# mainboard_1_3.net
KiCad netlist of a schematic drawn in EAGLE
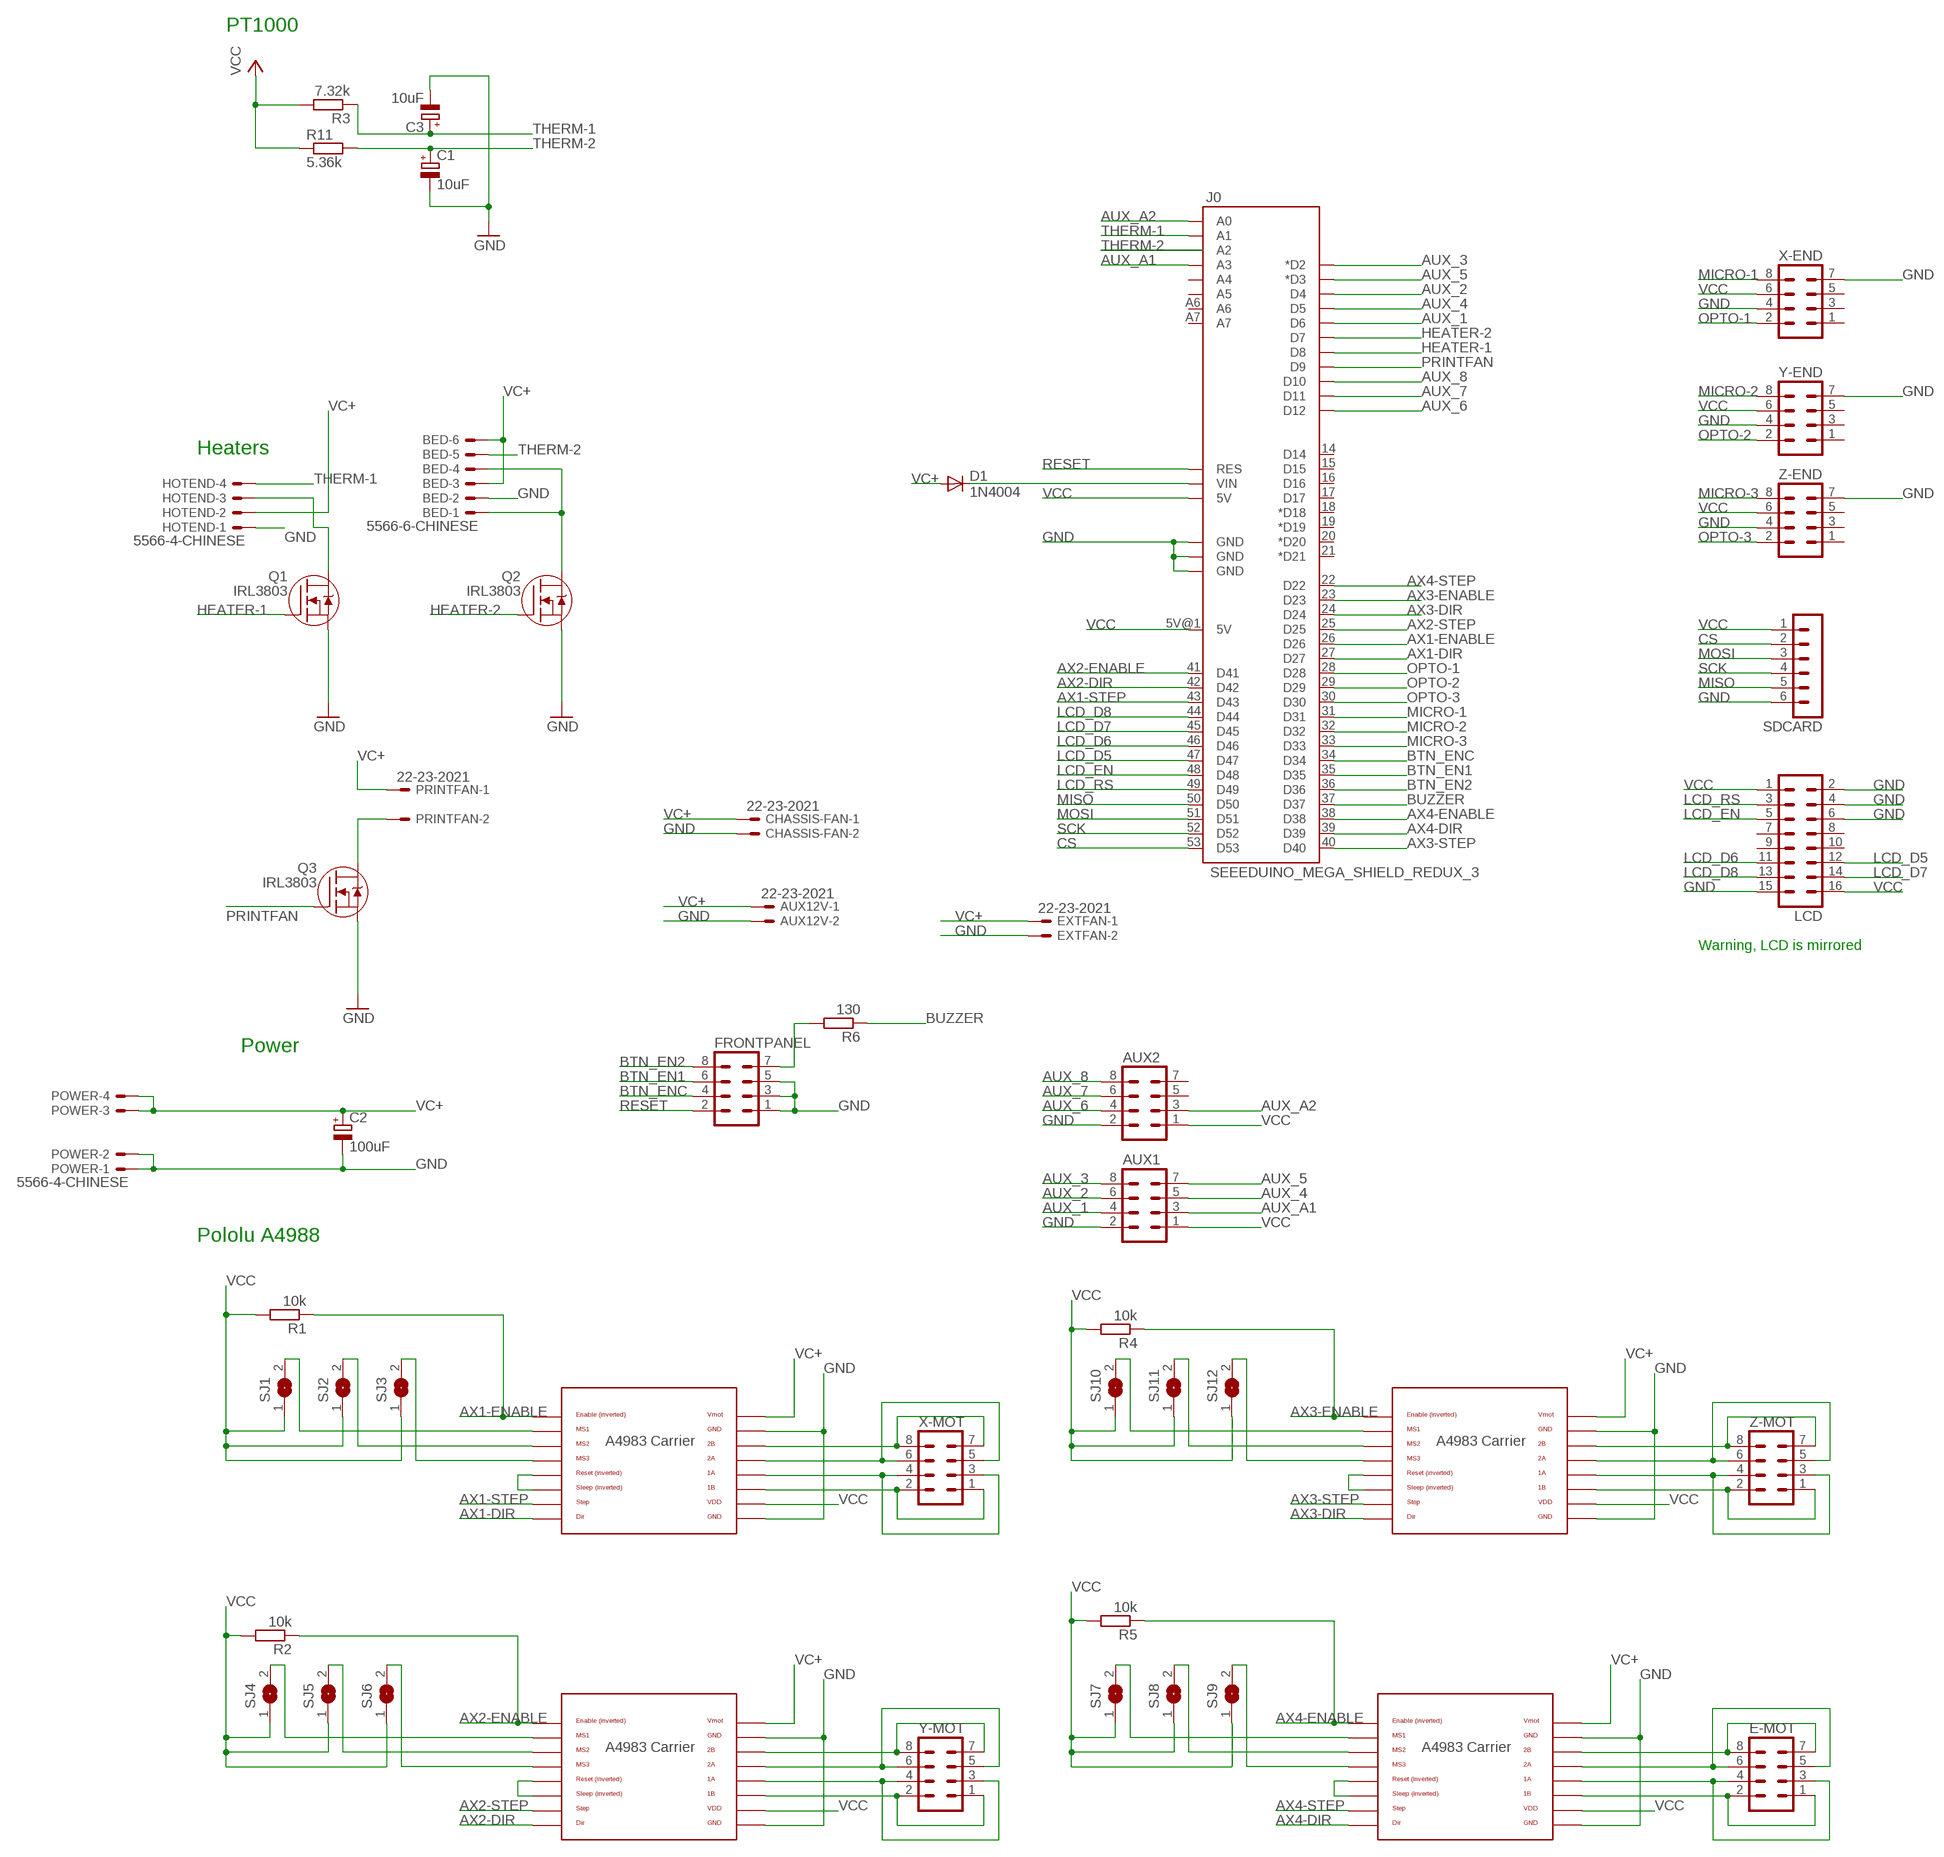
[diagram p0: schematic, sheet 1]

(export (version "E")
  (design (tool "Eeschema 10.0.6"))
  (components
    (comp (ref "AUX1")
      (value "MA04-2-HOLES")
      (footprint "eagle-import:MA04-2")
      (fields (field (name "OC_FARNELL") "unknown") (field (name "OC_NEWARK") "unknown"))
      (libsource (lib "eagle-import") (part "MA04-2-HOLES"))
    )
    (comp (ref "AUX2")
      (value "MA04-2")
      (footprint "eagle-import:MA04-2@1")
      (fields (field (name "OC_FARNELL") "unknown") (field (name "OC_NEWARK") "unknown"))
      (libsource (lib "eagle-import") (part "MA04-2"))
    )
    (comp (ref "AUX12V")
      (value "22-23-2021")
      (footprint "eagle-import:22-23-2021")
      (fields
        (field (name "MF") "MOLEX")
        (field (name "MF_1") "MOLEX")
        (field (name "MPN") "22-23-2021")
        (field (name "OC_FARNELL") "1462926")
        (field (name "OC_NEWARK") "25C3832")
      )
      (libsource (lib "eagle-import") (part "22-23-2021"))
    )
    (comp (ref "BED")
      (value "5566-6-CHINESE")
      (footprint "eagle-import:5566-6-CHINESE")
      (fields (field (name "MPN") "95566-61002"))
      (libsource (lib "eagle-import") (part "5566-6-CHINESE"))
    )
    (comp (ref "C1")
      (value "10uF")
      (footprint "eagle-import:E2,5-6")
      (libsource (lib "eagle-import") (part "CPOL-EUE2.5-6"))
    )
    (comp (ref "C2")
      (value "100uF")
      (footprint "eagle-import:E2,5-6")
      (libsource (lib "eagle-import") (part "CPOL-EUE2.5-6"))
    )
    (comp (ref "C3")
      (value "10uF")
      (footprint "eagle-import:E2,5-6")
      (libsource (lib "eagle-import") (part "CPOL-EUE2.5-6"))
    )
    (comp (ref "CHASSIS-FAN")
      (value "22-23-2021")
      (footprint "eagle-import:22-23-2021")
      (fields
        (field (name "MF") "MOLEX")
        (field (name "MF_1") "MOLEX")
        (field (name "MPN") "22-23-2021")
        (field (name "OC_FARNELL") "1462926")
        (field (name "OC_NEWARK") "25C3832")
      )
      (libsource (lib "eagle-import") (part "22-23-2021"))
    )
    (comp (ref "D1")
      (value "1N4004")
      (footprint "eagle-import:DO41-10")
      (libsource (lib "eagle-import") (part "1N4004"))
    )
    (comp (ref "E-AXIS")
      (value "POLOLU_A4983CARRIER")
      (footprint "eagle-import:A4983CARRIER")
      (libsource (lib "eagle-import") (part "POLOLU_A4983CARRIER"))
    )
    (comp (ref "E-MOT")
      (value "MA04-2")
      (footprint "eagle-import:MA04-2@1")
      (libsource (lib "eagle-import") (part "MA04-2"))
    )
    (comp (ref "EXTFAN")
      (value "22-23-2021")
      (footprint "eagle-import:22-23-2021")
      (fields
        (field (name "MF") "MOLEX")
        (field (name "MF_1") "MOLEX")
        (field (name "MPN") "22-23-2021")
        (field (name "OC_FARNELL") "1462926")
        (field (name "OC_NEWARK") "25C3832")
      )
      (libsource (lib "eagle-import") (part "22-23-2021"))
    )
    (comp (ref "FRONTPANEL")
      (value "MA04-2")
      (footprint "eagle-import:MA04-2@1")
      (libsource (lib "eagle-import") (part "MA04-2"))
    )
    (comp (ref "HOTEND")
      (value "5566-4-CHINESE")
      (footprint "eagle-import:5566-4-CHINESE")
      (libsource (lib "eagle-import") (part "5566-4-CHINESE"))
    )
    (comp (ref "J0")
      (value "SEEEDUINO_MEGA_SHIELD_REDUX_3")
      (footprint "eagle-import:SEEEDUINO_MEGA_SHIELD_REDUX_3")
      (libsource (lib "eagle-import") (part "SEEEDUINO_MEGA_SHIELD_REDUX_3"))
    )
    (comp (ref "LCD")
      (value "MA08-2")
      (footprint "eagle-import:MA08-2")
      (libsource (lib "eagle-import") (part "MA08-2"))
    )
    (comp (ref "POWER")
      (value "5566-4-CHINESE")
      (footprint "eagle-import:5566-4-CHINESE")
      (libsource (lib "eagle-import") (part "5566-4-CHINESE"))
    )
    (comp (ref "PRINTFAN")
      (value "22-23-2021")
      (footprint "eagle-import:22-23-2021")
      (fields (field (name "MF") "MOLEX"))
      (libsource (lib "eagle-import") (part "22-23-2021"))
    )
    (comp (ref "Q1")
      (value "IRL3803")
      (footprint "eagle-import:TO220AB")
      (libsource (lib "eagle-import") (part "IRL3803"))
    )
    (comp (ref "Q2")
      (value "IRL3803")
      (footprint "eagle-import:TO220AB")
      (libsource (lib "eagle-import") (part "IRL3803"))
    )
    (comp (ref "Q3")
      (value "IRL3803")
      (footprint "eagle-import:TO220AB")
      (libsource (lib "eagle-import") (part "IRL3803"))
    )
    (comp (ref "R1")
      (value "10k")
      (footprint "eagle-import:0204_7")
      (libsource (lib "eagle-import") (part "R-EU_0204/7"))
    )
    (comp (ref "R2")
      (value "10k")
      (footprint "eagle-import:0204_7")
      (libsource (lib "eagle-import") (part "R-EU_0204/7"))
    )
    (comp (ref "R3")
      (value "7.32k")
      (footprint "eagle-import:0204_7")
      (libsource (lib "eagle-import") (part "R-EU_0204/7"))
    )
    (comp (ref "R4")
      (value "10k")
      (footprint "eagle-import:0204_7")
      (libsource (lib "eagle-import") (part "R-EU_0204/7"))
    )
    (comp (ref "R5")
      (value "10k")
      (footprint "eagle-import:0204_7")
      (libsource (lib "eagle-import") (part "R-EU_0204/7"))
    )
    (comp (ref "R6")
      (value "130")
      (footprint "eagle-import:0204_7")
      (libsource (lib "eagle-import") (part "R-EU_0204/7"))
    )
    (comp (ref "R11")
      (value "5.36k")
      (footprint "eagle-import:0204_7")
      (libsource (lib "eagle-import") (part "R-EU_0204/7"))
    )
    (comp (ref "SDCARD")
      (value "MA06-1")
      (footprint "eagle-import:MA06-1")
      (libsource (lib "eagle-import") (part "MA06-1"))
    )
    (comp (ref "SJ1") (value "SJ") (footprint "eagle-import:SJ") (libsource (lib "eagle-import") (part "SJ")))
    (comp (ref "SJ2") (value "SJ") (footprint "eagle-import:SJ") (libsource (lib "eagle-import") (part "SJ")))
    (comp (ref "SJ3") (value "SJ") (footprint "eagle-import:SJ") (libsource (lib "eagle-import") (part "SJ")))
    (comp (ref "SJ4") (value "SJ") (footprint "eagle-import:SJ") (libsource (lib "eagle-import") (part "SJ")))
    (comp (ref "SJ5") (value "SJ") (footprint "eagle-import:SJ") (libsource (lib "eagle-import") (part "SJ")))
    (comp (ref "SJ6") (value "SJ") (footprint "eagle-import:SJ") (libsource (lib "eagle-import") (part "SJ")))
    (comp (ref "SJ7") (value "SJ") (footprint "eagle-import:SJ") (libsource (lib "eagle-import") (part "SJ")))
    (comp (ref "SJ8") (value "SJ") (footprint "eagle-import:SJ") (libsource (lib "eagle-import") (part "SJ")))
    (comp (ref "SJ9") (value "SJ") (footprint "eagle-import:SJ") (libsource (lib "eagle-import") (part "SJ")))
    (comp (ref "SJ10")
      (value "SJ")
      (footprint "eagle-import:SJ")
      (libsource (lib "eagle-import") (part "SJ"))
    )
    (comp (ref "SJ11")
      (value "SJ")
      (footprint "eagle-import:SJ")
      (libsource (lib "eagle-import") (part "SJ"))
    )
    (comp (ref "SJ12")
      (value "SJ")
      (footprint "eagle-import:SJ")
      (libsource (lib "eagle-import") (part "SJ"))
    )
    (comp (ref "X-AXIS")
      (value "POLOLU_A4983CARRIER")
      (footprint "eagle-import:A4983CARRIER")
      (libsource (lib "eagle-import") (part "POLOLU_A4983CARRIER"))
    )
    (comp (ref "X-END")
      (value "MA04-2")
      (footprint "eagle-import:MA04-2@1")
      (fields (field (name "OC_FARNELL") "unknown") (field (name "OC_NEWARK") "unknown"))
      (libsource (lib "eagle-import") (part "MA04-2"))
    )
    (comp (ref "X-MOT")
      (value "MA04-2")
      (footprint "eagle-import:MA04-2@1")
      (libsource (lib "eagle-import") (part "MA04-2"))
    )
    (comp (ref "Y-AXIS")
      (value "POLOLU_A4983CARRIER")
      (footprint "eagle-import:A4983CARRIER")
      (libsource (lib "eagle-import") (part "POLOLU_A4983CARRIER"))
    )
    (comp (ref "Y-END")
      (value "MA04-2")
      (footprint "eagle-import:MA04-2@1")
      (fields (field (name "OC_FARNELL") "unknown") (field (name "OC_NEWARK") "unknown"))
      (libsource (lib "eagle-import") (part "MA04-2"))
    )
    (comp (ref "Y-MOT")
      (value "MA04-2")
      (footprint "eagle-import:MA04-2@1")
      (libsource (lib "eagle-import") (part "MA04-2"))
    )
    (comp (ref "Z-AXIS")
      (value "POLOLU_A4983CARRIER")
      (footprint "eagle-import:A4983CARRIER")
      (libsource (lib "eagle-import") (part "POLOLU_A4983CARRIER"))
    )
    (comp (ref "Z-END")
      (value "MA04-2")
      (footprint "eagle-import:MA04-2@1")
      (fields (field (name "OC_FARNELL") "unknown") (field (name "OC_NEWARK") "unknown"))
      (libsource (lib "eagle-import") (part "MA04-2"))
    )
    (comp (ref "Z-MOT")
      (value "MA04-2")
      (footprint "eagle-import:MA04-2@1")
      (libsource (lib "eagle-import") (part "MA04-2"))
    )
  )
  (nets
    (net (code "1") (name "/AUX_1") (class "Default")
      (node (ref "AUX1") (pin "4") (pinfunction "4_4") (pintype "passive"))
      (node (ref "J0") (pin "6") (pinfunction "D6_6") (pintype "bidirectional"))
    )
    (net (code "2") (name "/AUX_2") (class "Default")
      (node (ref "AUX1") (pin "6") (pinfunction "6_6") (pintype "passive"))
      (node (ref "J0") (pin "4") (pinfunction "D4_4") (pintype "bidirectional"))
    )
    (net (code "3") (name "/AUX_3") (class "Default")
      (node (ref "AUX1") (pin "8") (pinfunction "8_8") (pintype "passive"))
      (node (ref "J0") (pin "2") (pinfunction "*D2_2") (pintype "bidirectional"))
    )
    (net (code "4") (name "/AUX_4") (class "Default")
      (node (ref "AUX1") (pin "5") (pinfunction "5_5") (pintype "passive"))
      (node (ref "J0") (pin "5") (pinfunction "D5_5") (pintype "bidirectional"))
    )
    (net (code "5") (name "/AUX_5") (class "Default")
      (node (ref "AUX1") (pin "7") (pinfunction "7_7") (pintype "passive"))
      (node (ref "J0") (pin "3") (pinfunction "*D3_3") (pintype "bidirectional"))
    )
    (net (code "6") (name "/AUX_6") (class "Default")
      (node (ref "AUX2") (pin "4") (pinfunction "4_4") (pintype "passive"))
      (node (ref "J0") (pin "12") (pinfunction "D12_12") (pintype "bidirectional"))
    )
    (net (code "7") (name "/AUX_7") (class "Default")
      (node (ref "AUX2") (pin "6") (pinfunction "6_6") (pintype "passive"))
      (node (ref "J0") (pin "11") (pinfunction "D11_11") (pintype "bidirectional"))
    )
    (net (code "8") (name "/AUX_8") (class "Default")
      (node (ref "AUX2") (pin "8") (pinfunction "8_8") (pintype "passive"))
      (node (ref "J0") (pin "10") (pinfunction "D10_10") (pintype "bidirectional"))
    )
    (net (code "9") (name "/AUX_A1") (class "Default")
      (node (ref "AUX1") (pin "3") (pinfunction "3_3") (pintype "passive"))
      (node (ref "J0") (pin "A3") (pinfunction "A3_A3") (pintype "bidirectional"))
    )
    (net (code "10") (name "/AUX_A2") (class "Default")
      (node (ref "AUX2") (pin "3") (pinfunction "3_3") (pintype "passive"))
      (node (ref "J0") (pin "A0") (pinfunction "A0_A0") (pintype "bidirectional"))
    )
    (net (code "11") (name "/AX1-DIR") (class "Default")
      (node (ref "J0") (pin "27") (pinfunction "D27_27") (pintype "bidirectional"))
      (node (ref "X-AXIS") (pin "DIR") (pinfunction "DIR_DIR") (pintype "input"))
    )
    (net (code "12") (name "/AX1-ENABLE") (class "Default")
      (node (ref "J0") (pin "26") (pinfunction "D26_26") (pintype "bidirectional"))
      (node (ref "R1") (pin "1") (pinfunction "1_1") (pintype "passive"))
      (node (ref "X-AXIS") (pin "EN") (pinfunction "EN_EN") (pintype "input"))
    )
    (net (code "13") (name "/AX1-STEP") (class "Default")
      (node (ref "J0") (pin "43") (pinfunction "D43_43") (pintype "bidirectional"))
      (node (ref "X-AXIS") (pin "STEP") (pinfunction "STEP_STEP") (pintype "input"))
    )
    (net (code "14") (name "/AX2-DIR") (class "Default")
      (node (ref "J0") (pin "42") (pinfunction "D42_42") (pintype "bidirectional"))
      (node (ref "Y-AXIS") (pin "DIR") (pinfunction "DIR_DIR") (pintype "input"))
    )
    (net (code "15") (name "/AX2-ENABLE") (class "Default")
      (node (ref "J0") (pin "41") (pinfunction "D41_41") (pintype "bidirectional"))
      (node (ref "R2") (pin "1") (pinfunction "1_1") (pintype "passive"))
      (node (ref "Y-AXIS") (pin "EN") (pinfunction "EN_EN") (pintype "input"))
    )
    (net (code "16") (name "/AX2-STEP") (class "Default")
      (node (ref "J0") (pin "25") (pinfunction "D25_25") (pintype "bidirectional"))
      (node (ref "Y-AXIS") (pin "STEP") (pinfunction "STEP_STEP") (pintype "input"))
    )
    (net (code "17") (name "/AX3-DIR") (class "Default")
      (node (ref "J0") (pin "24") (pinfunction "D24_24") (pintype "bidirectional"))
      (node (ref "Z-AXIS") (pin "DIR") (pinfunction "DIR_DIR") (pintype "input"))
    )
    (net (code "18") (name "/AX3-ENABLE") (class "Default")
      (node (ref "J0") (pin "23") (pinfunction "D23_23") (pintype "bidirectional"))
      (node (ref "R4") (pin "1") (pinfunction "1_1") (pintype "passive"))
      (node (ref "Z-AXIS") (pin "EN") (pinfunction "EN_EN") (pintype "input"))
    )
    (net (code "19") (name "/AX3-STEP") (class "Default")
      (node (ref "J0") (pin "40") (pinfunction "D40_40") (pintype "bidirectional"))
      (node (ref "Z-AXIS") (pin "STEP") (pinfunction "STEP_STEP") (pintype "input"))
    )
    (net (code "20") (name "/AX4-DIR") (class "Default")
      (node (ref "E-AXIS") (pin "DIR") (pinfunction "DIR_DIR") (pintype "input"))
      (node (ref "J0") (pin "39") (pinfunction "D39_39") (pintype "bidirectional"))
    )
    (net (code "21") (name "/AX4-ENABLE") (class "Default")
      (node (ref "E-AXIS") (pin "EN") (pinfunction "EN_EN") (pintype "input"))
      (node (ref "J0") (pin "38") (pinfunction "D38_38") (pintype "bidirectional"))
      (node (ref "R5") (pin "1") (pinfunction "1_1") (pintype "passive"))
    )
    (net (code "22") (name "/AX4-STEP") (class "Default")
      (node (ref "E-AXIS") (pin "STEP") (pinfunction "STEP_STEP") (pintype "input"))
      (node (ref "J0") (pin "22") (pinfunction "D22_22") (pintype "bidirectional"))
    )
    (net (code "23") (name "/BTN_EN1") (class "Default")
      (node (ref "FRONTPANEL") (pin "6") (pinfunction "6_6") (pintype "passive"))
      (node (ref "J0") (pin "35") (pinfunction "D35_35") (pintype "bidirectional"))
    )
    (net (code "24") (name "/BTN_EN2") (class "Default")
      (node (ref "FRONTPANEL") (pin "8") (pinfunction "8_8") (pintype "passive"))
      (node (ref "J0") (pin "36") (pinfunction "D36_36") (pintype "bidirectional"))
    )
    (net (code "25") (name "/BTN_ENC") (class "Default")
      (node (ref "FRONTPANEL") (pin "4") (pinfunction "4_4") (pintype "passive"))
      (node (ref "J0") (pin "34") (pinfunction "D34_34") (pintype "bidirectional"))
    )
    (net (code "26") (name "/BUZZER") (class "Default")
      (node (ref "J0") (pin "37") (pinfunction "D37_37") (pintype "bidirectional"))
      (node (ref "R6") (pin "1") (pinfunction "1_1") (pintype "passive"))
    )
    (net (code "27") (name "/CS") (class "Default")
      (node (ref "J0") (pin "53") (pinfunction "D53_53") (pintype "bidirectional"))
      (node (ref "SDCARD") (pin "2") (pinfunction "2_2") (pintype "passive"))
    )
    (net (code "28") (name "/HEATER-1") (class "Default")
      (node (ref "J0") (pin "8") (pinfunction "D8_8") (pintype "bidirectional"))
      (node (ref "Q1") (pin "G") (pinfunction "G_G") (pintype "bidirectional"))
    )
    (net (code "29") (name "/HEATER-2") (class "Default")
      (node (ref "J0") (pin "7") (pinfunction "D7_7") (pintype "bidirectional"))
      (node (ref "Q2") (pin "G") (pinfunction "G_G") (pintype "bidirectional"))
    )
    (net (code "30") (name "/LCD_D5") (class "Default")
      (node (ref "J0") (pin "47") (pinfunction "D47_47") (pintype "bidirectional"))
      (node (ref "LCD") (pin "12") (pinfunction "12_12") (pintype "passive"))
    )
    (net (code "31") (name "/LCD_D6") (class "Default")
      (node (ref "J0") (pin "46") (pinfunction "D46_46") (pintype "bidirectional"))
      (node (ref "LCD") (pin "11") (pinfunction "11_11") (pintype "passive"))
    )
    (net (code "32") (name "/LCD_D7") (class "Default")
      (node (ref "J0") (pin "45") (pinfunction "D45_45") (pintype "bidirectional"))
      (node (ref "LCD") (pin "14") (pinfunction "14_14") (pintype "passive"))
    )
    (net (code "33") (name "/LCD_D8") (class "Default")
      (node (ref "J0") (pin "44") (pinfunction "D44_44") (pintype "bidirectional"))
      (node (ref "LCD") (pin "13") (pinfunction "13_13") (pintype "passive"))
    )
    (net (code "34") (name "/LCD_EN") (class "Default")
      (node (ref "J0") (pin "48") (pinfunction "D48_48") (pintype "bidirectional"))
      (node (ref "LCD") (pin "5") (pinfunction "5_5") (pintype "passive"))
    )
    (net (code "35") (name "/LCD_RS") (class "Default")
      (node (ref "J0") (pin "49") (pinfunction "D49_49") (pintype "bidirectional"))
      (node (ref "LCD") (pin "3") (pinfunction "3_3") (pintype "passive"))
    )
    (net (code "36") (name "/MICRO-1") (class "Default")
      (node (ref "J0") (pin "31") (pinfunction "D31_31") (pintype "bidirectional"))
      (node (ref "X-END") (pin "8") (pinfunction "8_8") (pintype "passive"))
    )
    (net (code "37") (name "/MICRO-2") (class "Default")
      (node (ref "J0") (pin "32") (pinfunction "D32_32") (pintype "bidirectional"))
      (node (ref "Y-END") (pin "8") (pinfunction "8_8") (pintype "passive"))
    )
    (net (code "38") (name "/MICRO-3") (class "Default")
      (node (ref "J0") (pin "33") (pinfunction "D33_33") (pintype "bidirectional"))
      (node (ref "Z-END") (pin "8") (pinfunction "8_8") (pintype "passive"))
    )
    (net (code "39") (name "/MISO") (class "Default")
      (node (ref "J0") (pin "50") (pinfunction "D50_50") (pintype "bidirectional"))
      (node (ref "SDCARD") (pin "5") (pinfunction "5_5") (pintype "passive"))
    )
    (net (code "40") (name "/MOSI") (class "Default")
      (node (ref "J0") (pin "51") (pinfunction "D51_51") (pintype "bidirectional"))
      (node (ref "SDCARD") (pin "3") (pinfunction "3_3") (pintype "passive"))
    )
    (net (code "41") (name "/OPTO-1") (class "Default")
      (node (ref "J0") (pin "28") (pinfunction "D28_28") (pintype "bidirectional"))
      (node (ref "X-END") (pin "2") (pinfunction "2_2") (pintype "passive"))
    )
    (net (code "42") (name "/OPTO-2") (class "Default")
      (node (ref "J0") (pin "29") (pinfunction "D29_29") (pintype "bidirectional"))
      (node (ref "Y-END") (pin "2") (pinfunction "2_2") (pintype "passive"))
    )
    (net (code "43") (name "/OPTO-3") (class "Default")
      (node (ref "J0") (pin "30") (pinfunction "D30_30") (pintype "bidirectional"))
      (node (ref "Z-END") (pin "2") (pinfunction "2_2") (pintype "passive"))
    )
    (net (code "44") (name "/PRINTFAN") (class "Default")
      (node (ref "J0") (pin "9") (pinfunction "D9_9") (pintype "bidirectional"))
      (node (ref "Q3") (pin "G") (pinfunction "G_G") (pintype "bidirectional"))
    )
    (net (code "45") (name "/RESET") (class "Default")
      (node (ref "FRONTPANEL") (pin "2") (pinfunction "2_2") (pintype "passive"))
      (node (ref "J0") (pin "RST") (pinfunction "RES_RST") (pintype "bidirectional"))
    )
    (net (code "46") (name "/SCK") (class "Default")
      (node (ref "J0") (pin "52") (pinfunction "D52_52") (pintype "bidirectional"))
      (node (ref "SDCARD") (pin "4") (pinfunction "4_4") (pintype "passive"))
    )
    (net (code "47") (name "/THERM-1") (class "Default")
      (node (ref "C3") (pin "+") (pinfunction "+_+") (pintype "passive"))
      (node (ref "HOTEND") (pin "4") (pinfunction "S_4") (pintype "passive"))
      (node (ref "J0") (pin "A1") (pinfunction "A1_A1") (pintype "bidirectional"))
      (node (ref "R3") (pin "1") (pinfunction "1_1") (pintype "passive"))
    )
    (net (code "48") (name "/THERM-2") (class "Default")
      (node (ref "BED") (pin "5") (pinfunction "S_5") (pintype "passive"))
      (node (ref "C1") (pin "+") (pinfunction "+_+") (pintype "passive"))
      (node (ref "J0") (pin "A2") (pinfunction "A2_A2") (pintype "bidirectional"))
      (node (ref "R11") (pin "2") (pinfunction "2_2") (pintype "passive"))
    )
    (net (code "49") (name "/VC+") (class "Default")
      (node (ref "AUX12V") (pin "1") (pinfunction "S_1") (pintype "passive"))
      (node (ref "BED") (pin "3") (pinfunction "S_3") (pintype "passive"))
      (node (ref "BED") (pin "6") (pinfunction "S_6") (pintype "passive"))
      (node (ref "C2") (pin "+") (pinfunction "+_+") (pintype "passive"))
      (node (ref "CHASSIS-FAN") (pin "1") (pinfunction "S_1") (pintype "passive"))
      (node (ref "D1") (pin "A") (pinfunction "A_A") (pintype "passive"))
      (node (ref "E-AXIS") (pin "VMOT") (pinfunction "VMOT_VMOT") (pintype "power_in"))
      (node (ref "EXTFAN") (pin "1") (pinfunction "S_1") (pintype "passive"))
      (node (ref "HOTEND") (pin "2") (pinfunction "S_2") (pintype "passive"))
      (node (ref "POWER") (pin "3") (pinfunction "S_3") (pintype "passive"))
      (node (ref "POWER") (pin "4") (pinfunction "S_4") (pintype "passive"))
      (node (ref "PRINTFAN") (pin "1") (pinfunction "S_1") (pintype "passive"))
      (node (ref "X-AXIS") (pin "VMOT") (pinfunction "VMOT_VMOT") (pintype "power_in"))
      (node (ref "Y-AXIS") (pin "VMOT") (pinfunction "VMOT_VMOT") (pintype "power_in"))
      (node (ref "Z-AXIS") (pin "VMOT") (pinfunction "VMOT_VMOT") (pintype "power_in"))
    )
    (net (code "50") (name "GND") (class "Default")
      (node (ref "AUX1") (pin "2") (pinfunction "2_2") (pintype "passive"))
      (node (ref "AUX12V") (pin "2") (pinfunction "S_2") (pintype "passive"))
      (node (ref "AUX2") (pin "2") (pinfunction "2_2") (pintype "passive"))
      (node (ref "BED") (pin "2") (pinfunction "S_2") (pintype "passive"))
      (node (ref "C1") (pin "-") (pinfunction "-_-") (pintype "passive"))
      (node (ref "C2") (pin "-") (pinfunction "-_-") (pintype "passive"))
      (node (ref "C3") (pin "-") (pinfunction "-_-") (pintype "passive"))
      (node (ref "CHASSIS-FAN") (pin "2") (pinfunction "S_2") (pintype "passive"))
      (node (ref "E-AXIS") (pin "GND") (pinfunction "GND_GND") (pintype "power_in"))
      (node (ref "E-AXIS") (pin "GND@0") (pinfunction "GND_GND@0") (pintype "power_in"))
      (node (ref "EXTFAN") (pin "2") (pinfunction "S_2") (pintype "passive"))
      (node (ref "FRONTPANEL") (pin "1") (pinfunction "1_1") (pintype "passive"))
      (node (ref "FRONTPANEL") (pin "3") (pinfunction "3_3") (pintype "passive"))
      (node (ref "FRONTPANEL") (pin "5") (pinfunction "5_5") (pintype "passive"))
      (node (ref "HOTEND") (pin "1") (pinfunction "S_1") (pintype "passive"))
      (node (ref "J0") (pin "GND@0") (pinfunction "GND_GND@0") (pintype "power_in"))
      (node (ref "J0") (pin "GND@1") (pinfunction "GND_GND@1") (pintype "power_in"))
      (node (ref "J0") (pin "GND@2") (pinfunction "GND_GND@2") (pintype "power_in"))
      (node (ref "LCD") (pin "15") (pinfunction "15_15") (pintype "passive"))
      (node (ref "LCD") (pin "2") (pinfunction "2_2") (pintype "passive"))
      (node (ref "LCD") (pin "4") (pinfunction "4_4") (pintype "passive"))
      (node (ref "LCD") (pin "6") (pinfunction "6_6") (pintype "passive"))
      (node (ref "POWER") (pin "1") (pinfunction "S_1") (pintype "passive"))
      (node (ref "POWER") (pin "2") (pinfunction "S_2") (pintype "passive"))
      (node (ref "Q1") (pin "S") (pinfunction "S_S") (pintype "bidirectional"))
      (node (ref "Q2") (pin "S") (pinfunction "S_S") (pintype "bidirectional"))
      (node (ref "Q3") (pin "S") (pinfunction "S_S") (pintype "bidirectional"))
      (node (ref "SDCARD") (pin "6") (pinfunction "6_6") (pintype "passive"))
      (node (ref "X-AXIS") (pin "GND") (pinfunction "GND_GND") (pintype "power_in"))
      (node (ref "X-AXIS") (pin "GND@0") (pinfunction "GND_GND@0") (pintype "power_in"))
      (node (ref "X-END") (pin "4") (pinfunction "4_4") (pintype "passive"))
      (node (ref "X-END") (pin "7") (pinfunction "7_7") (pintype "passive"))
      (node (ref "Y-AXIS") (pin "GND") (pinfunction "GND_GND") (pintype "power_in"))
      (node (ref "Y-AXIS") (pin "GND@0") (pinfunction "GND_GND@0") (pintype "power_in"))
      (node (ref "Y-END") (pin "4") (pinfunction "4_4") (pintype "passive"))
      (node (ref "Y-END") (pin "7") (pinfunction "7_7") (pintype "passive"))
      (node (ref "Z-AXIS") (pin "GND") (pinfunction "GND_GND") (pintype "power_in"))
      (node (ref "Z-AXIS") (pin "GND@0") (pinfunction "GND_GND@0") (pintype "power_in"))
      (node (ref "Z-END") (pin "4") (pinfunction "4_4") (pintype "passive"))
      (node (ref "Z-END") (pin "7") (pinfunction "7_7") (pintype "passive"))
    )
    (net (code "51") (name "Net-(BEDA-S)") (class "Default")
      (node (ref "BED") (pin "1") (pinfunction "S_1") (pintype "passive"))
      (node (ref "BED") (pin "4") (pinfunction "S_4") (pintype "passive"))
      (node (ref "Q2") (pin "D") (pinfunction "D_D") (pintype "bidirectional"))
    )
    (net (code "52") (name "Net-(D1-PadC)") (class "Default")
      (node (ref "D1") (pin "C") (pinfunction "C_C") (pintype "passive"))
      (node (ref "J0") (pin "VIN") (pinfunction "VIN_VIN") (pintype "bidirectional"))
    )
    (net (code "53") (name "Net-(E-AXIS-Pad1A)") (class "Default")
      (node (ref "E-AXIS") (pin "1A") (pinfunction "1A_1A") (pintype "output"))
      (node (ref "E-MOT") (pin "3") (pinfunction "3_3") (pintype "passive"))
      (node (ref "E-MOT") (pin "4") (pinfunction "4_4") (pintype "passive"))
    )
    (net (code "54") (name "Net-(E-AXIS-Pad1B)") (class "Default")
      (node (ref "E-AXIS") (pin "1B") (pinfunction "1B_1B") (pintype "output"))
      (node (ref "E-MOT") (pin "1") (pinfunction "1_1") (pintype "passive"))
      (node (ref "E-MOT") (pin "2") (pinfunction "2_2") (pintype "passive"))
    )
    (net (code "55") (name "Net-(E-AXIS-Pad2A)") (class "Default")
      (node (ref "E-AXIS") (pin "2A") (pinfunction "2A_2A") (pintype "output"))
      (node (ref "E-MOT") (pin "5") (pinfunction "5_5") (pintype "passive"))
      (node (ref "E-MOT") (pin "6") (pinfunction "6_6") (pintype "passive"))
    )
    (net (code "56") (name "Net-(E-AXIS-Pad2B)") (class "Default")
      (node (ref "E-AXIS") (pin "2B") (pinfunction "2B_2B") (pintype "output"))
      (node (ref "E-MOT") (pin "7") (pinfunction "7_7") (pintype "passive"))
      (node (ref "E-MOT") (pin "8") (pinfunction "8_8") (pintype "passive"))
    )
    (net (code "57") (name "Net-(E-AXIS-PadMS1)") (class "Default")
      (node (ref "E-AXIS") (pin "MS1") (pinfunction "MS1_MS1") (pintype "input"))
      (node (ref "SJ7") (pin "2") (pinfunction "2_2") (pintype "passive"))
    )
    (net (code "58") (name "Net-(E-AXIS-PadMS2)") (class "Default")
      (node (ref "E-AXIS") (pin "MS2") (pinfunction "MS2_MS2") (pintype "input"))
      (node (ref "SJ8") (pin "2") (pinfunction "2_2") (pintype "passive"))
    )
    (net (code "59") (name "Net-(E-AXIS-PadMS3)") (class "Default")
      (node (ref "E-AXIS") (pin "MS3") (pinfunction "MS3_MS3") (pintype "input"))
      (node (ref "SJ9") (pin "2") (pinfunction "2_2") (pintype "passive"))
    )
    (net (code "60") (name "Net-(E-AXIS-SLEEP)") (class "Default")
      (node (ref "E-AXIS") (pin "RST") (pinfunction "RST_RST") (pintype "input"))
      (node (ref "E-AXIS") (pin "SLP") (pinfunction "SLEEP_SLP") (pintype "input"))
    )
    (net (code "61") (name "Net-(FRONTPANEL-Pad7)") (class "Default")
      (node (ref "FRONTPANEL") (pin "7") (pinfunction "7_7") (pintype "passive"))
      (node (ref "R6") (pin "2") (pinfunction "2_2") (pintype "passive"))
    )
    (net (code "62") (name "Net-(HOTENDC-S)") (class "Default")
      (node (ref "HOTEND") (pin "3") (pinfunction "S_3") (pintype "passive"))
      (node (ref "Q1") (pin "D") (pinfunction "D_D") (pintype "bidirectional"))
    )
    (net (code "63") (name "Net-(PRINTFANB-S)") (class "Default")
      (node (ref "PRINTFAN") (pin "2") (pinfunction "S_2") (pintype "passive"))
      (node (ref "Q3") (pin "D") (pinfunction "D_D") (pintype "bidirectional"))
    )
    (net (code "64") (name "Net-(SJ1-Pad2)") (class "Default")
      (node (ref "SJ1") (pin "2") (pinfunction "2_2") (pintype "passive"))
      (node (ref "X-AXIS") (pin "MS1") (pinfunction "MS1_MS1") (pintype "input"))
    )
    (net (code "65") (name "Net-(SJ2-Pad2)") (class "Default")
      (node (ref "SJ2") (pin "2") (pinfunction "2_2") (pintype "passive"))
      (node (ref "X-AXIS") (pin "MS2") (pinfunction "MS2_MS2") (pintype "input"))
    )
    (net (code "66") (name "Net-(SJ3-Pad2)") (class "Default")
      (node (ref "SJ3") (pin "2") (pinfunction "2_2") (pintype "passive"))
      (node (ref "X-AXIS") (pin "MS3") (pinfunction "MS3_MS3") (pintype "input"))
    )
    (net (code "67") (name "Net-(SJ4-Pad2)") (class "Default")
      (node (ref "SJ4") (pin "2") (pinfunction "2_2") (pintype "passive"))
      (node (ref "Y-AXIS") (pin "MS1") (pinfunction "MS1_MS1") (pintype "input"))
    )
    (net (code "68") (name "Net-(SJ5-Pad2)") (class "Default")
      (node (ref "SJ5") (pin "2") (pinfunction "2_2") (pintype "passive"))
      (node (ref "Y-AXIS") (pin "MS2") (pinfunction "MS2_MS2") (pintype "input"))
    )
    (net (code "69") (name "Net-(SJ6-Pad2)") (class "Default")
      (node (ref "SJ6") (pin "2") (pinfunction "2_2") (pintype "passive"))
      (node (ref "Y-AXIS") (pin "MS3") (pinfunction "MS3_MS3") (pintype "input"))
    )
    (net (code "70") (name "Net-(SJ10-Pad2)") (class "Default")
      (node (ref "SJ10") (pin "2") (pinfunction "2_2") (pintype "passive"))
      (node (ref "Z-AXIS") (pin "MS1") (pinfunction "MS1_MS1") (pintype "input"))
    )
    (net (code "71") (name "Net-(SJ11-Pad2)") (class "Default")
      (node (ref "SJ11") (pin "2") (pinfunction "2_2") (pintype "passive"))
      (node (ref "Z-AXIS") (pin "MS2") (pinfunction "MS2_MS2") (pintype "input"))
    )
    (net (code "72") (name "Net-(SJ12-Pad2)") (class "Default")
      (node (ref "SJ12") (pin "2") (pinfunction "2_2") (pintype "passive"))
      (node (ref "Z-AXIS") (pin "MS3") (pinfunction "MS3_MS3") (pintype "input"))
    )
    (net (code "73") (name "Net-(X-AXIS-Pad1A)") (class "Default")
      (node (ref "X-AXIS") (pin "1A") (pinfunction "1A_1A") (pintype "output"))
      (node (ref "X-MOT") (pin "3") (pinfunction "3_3") (pintype "passive"))
      (node (ref "X-MOT") (pin "4") (pinfunction "4_4") (pintype "passive"))
    )
    (net (code "74") (name "Net-(X-AXIS-Pad1B)") (class "Default")
      (node (ref "X-AXIS") (pin "1B") (pinfunction "1B_1B") (pintype "output"))
      (node (ref "X-MOT") (pin "1") (pinfunction "1_1") (pintype "passive"))
      (node (ref "X-MOT") (pin "2") (pinfunction "2_2") (pintype "passive"))
    )
    (net (code "75") (name "Net-(X-AXIS-Pad2A)") (class "Default")
      (node (ref "X-AXIS") (pin "2A") (pinfunction "2A_2A") (pintype "output"))
      (node (ref "X-MOT") (pin "5") (pinfunction "5_5") (pintype "passive"))
      (node (ref "X-MOT") (pin "6") (pinfunction "6_6") (pintype "passive"))
    )
    (net (code "76") (name "Net-(X-AXIS-Pad2B)") (class "Default")
      (node (ref "X-AXIS") (pin "2B") (pinfunction "2B_2B") (pintype "output"))
      (node (ref "X-MOT") (pin "7") (pinfunction "7_7") (pintype "passive"))
      (node (ref "X-MOT") (pin "8") (pinfunction "8_8") (pintype "passive"))
    )
    (net (code "77") (name "Net-(X-AXIS-SLEEP)") (class "Default")
      (node (ref "X-AXIS") (pin "RST") (pinfunction "RST_RST") (pintype "input"))
      (node (ref "X-AXIS") (pin "SLP") (pinfunction "SLEEP_SLP") (pintype "input"))
    )
    (net (code "78") (name "Net-(Y-AXIS-Pad1A)") (class "Default")
      (node (ref "Y-AXIS") (pin "1A") (pinfunction "1A_1A") (pintype "output"))
      (node (ref "Y-MOT") (pin "3") (pinfunction "3_3") (pintype "passive"))
      (node (ref "Y-MOT") (pin "4") (pinfunction "4_4") (pintype "passive"))
    )
    (net (code "79") (name "Net-(Y-AXIS-Pad1B)") (class "Default")
      (node (ref "Y-AXIS") (pin "1B") (pinfunction "1B_1B") (pintype "output"))
      (node (ref "Y-MOT") (pin "1") (pinfunction "1_1") (pintype "passive"))
      (node (ref "Y-MOT") (pin "2") (pinfunction "2_2") (pintype "passive"))
    )
    (net (code "80") (name "Net-(Y-AXIS-Pad2A)") (class "Default")
      (node (ref "Y-AXIS") (pin "2A") (pinfunction "2A_2A") (pintype "output"))
      (node (ref "Y-MOT") (pin "5") (pinfunction "5_5") (pintype "passive"))
      (node (ref "Y-MOT") (pin "6") (pinfunction "6_6") (pintype "passive"))
    )
    (net (code "81") (name "Net-(Y-AXIS-Pad2B)") (class "Default")
      (node (ref "Y-AXIS") (pin "2B") (pinfunction "2B_2B") (pintype "output"))
      (node (ref "Y-MOT") (pin "7") (pinfunction "7_7") (pintype "passive"))
      (node (ref "Y-MOT") (pin "8") (pinfunction "8_8") (pintype "passive"))
    )
    (net (code "82") (name "Net-(Y-AXIS-SLEEP)") (class "Default")
      (node (ref "Y-AXIS") (pin "RST") (pinfunction "RST_RST") (pintype "input"))
      (node (ref "Y-AXIS") (pin "SLP") (pinfunction "SLEEP_SLP") (pintype "input"))
    )
    (net (code "83") (name "Net-(Z-AXIS-Pad1A)") (class "Default")
      (node (ref "Z-AXIS") (pin "1A") (pinfunction "1A_1A") (pintype "output"))
      (node (ref "Z-MOT") (pin "3") (pinfunction "3_3") (pintype "passive"))
      (node (ref "Z-MOT") (pin "4") (pinfunction "4_4") (pintype "passive"))
    )
    (net (code "84") (name "Net-(Z-AXIS-Pad1B)") (class "Default")
      (node (ref "Z-AXIS") (pin "1B") (pinfunction "1B_1B") (pintype "output"))
      (node (ref "Z-MOT") (pin "1") (pinfunction "1_1") (pintype "passive"))
      (node (ref "Z-MOT") (pin "2") (pinfunction "2_2") (pintype "passive"))
    )
    (net (code "85") (name "Net-(Z-AXIS-Pad2A)") (class "Default")
      (node (ref "Z-AXIS") (pin "2A") (pinfunction "2A_2A") (pintype "output"))
      (node (ref "Z-MOT") (pin "5") (pinfunction "5_5") (pintype "passive"))
      (node (ref "Z-MOT") (pin "6") (pinfunction "6_6") (pintype "passive"))
    )
    (net (code "86") (name "Net-(Z-AXIS-Pad2B)") (class "Default")
      (node (ref "Z-AXIS") (pin "2B") (pinfunction "2B_2B") (pintype "output"))
      (node (ref "Z-MOT") (pin "7") (pinfunction "7_7") (pintype "passive"))
      (node (ref "Z-MOT") (pin "8") (pinfunction "8_8") (pintype "passive"))
    )
    (net (code "87") (name "Net-(Z-AXIS-SLEEP)") (class "Default")
      (node (ref "Z-AXIS") (pin "RST") (pinfunction "RST_RST") (pintype "input"))
      (node (ref "Z-AXIS") (pin "SLP") (pinfunction "SLEEP_SLP") (pintype "input"))
    )
    (net (code "88") (name "VCC") (class "Default")
      (node (ref "AUX1") (pin "1") (pinfunction "1_1") (pintype "passive"))
      (node (ref "AUX2") (pin "1") (pinfunction "1_1") (pintype "passive"))
      (node (ref "E-AXIS") (pin "VDD") (pinfunction "VDD_VDD") (pintype "power_in"))
      (node (ref "J0") (pin "5V@0") (pinfunction "5V_5V@0") (pintype "power_in"))
      (node (ref "J0") (pin "5V@1") (pinfunction "5V_5V@1") (pintype "power_in"))
      (node (ref "LCD") (pin "1") (pinfunction "1_1") (pintype "passive"))
      (node (ref "LCD") (pin "16") (pinfunction "16_16") (pintype "passive"))
      (node (ref "R1") (pin "2") (pinfunction "2_2") (pintype "passive"))
      (node (ref "R11") (pin "1") (pinfunction "1_1") (pintype "passive"))
      (node (ref "R2") (pin "2") (pinfunction "2_2") (pintype "passive"))
      (node (ref "R3") (pin "2") (pinfunction "2_2") (pintype "passive"))
      (node (ref "R4") (pin "2") (pinfunction "2_2") (pintype "passive"))
      (node (ref "R5") (pin "2") (pinfunction "2_2") (pintype "passive"))
      (node (ref "SDCARD") (pin "1") (pinfunction "1_1") (pintype "passive"))
      (node (ref "SJ1") (pin "1") (pinfunction "1_1") (pintype "passive"))
      (node (ref "SJ10") (pin "1") (pinfunction "1_1") (pintype "passive"))
      (node (ref "SJ11") (pin "1") (pinfunction "1_1") (pintype "passive"))
      (node (ref "SJ12") (pin "1") (pinfunction "1_1") (pintype "passive"))
      (node (ref "SJ2") (pin "1") (pinfunction "1_1") (pintype "passive"))
      (node (ref "SJ3") (pin "1") (pinfunction "1_1") (pintype "passive"))
      (node (ref "SJ4") (pin "1") (pinfunction "1_1") (pintype "passive"))
      (node (ref "SJ5") (pin "1") (pinfunction "1_1") (pintype "passive"))
      (node (ref "SJ6") (pin "1") (pinfunction "1_1") (pintype "passive"))
      (node (ref "SJ7") (pin "1") (pinfunction "1_1") (pintype "passive"))
      (node (ref "SJ8") (pin "1") (pinfunction "1_1") (pintype "passive"))
      (node (ref "SJ9") (pin "1") (pinfunction "1_1") (pintype "passive"))
      (node (ref "X-AXIS") (pin "VDD") (pinfunction "VDD_VDD") (pintype "power_in"))
      (node (ref "X-END") (pin "6") (pinfunction "6_6") (pintype "passive"))
      (node (ref "Y-AXIS") (pin "VDD") (pinfunction "VDD_VDD") (pintype "power_in"))
      (node (ref "Y-END") (pin "6") (pinfunction "6_6") (pintype "passive"))
      (node (ref "Z-AXIS") (pin "VDD") (pinfunction "VDD_VDD") (pintype "power_in"))
      (node (ref "Z-END") (pin "6") (pinfunction "6_6") (pintype "passive"))
    )
    (net (code "89") (name "unconnected-(AUX2-Pad5)") (class "Default")
      (node (ref "AUX2") (pin "5") (pinfunction "5_5") (pintype "passive"))
    )
    (net (code "90") (name "unconnected-(AUX2-Pad7)") (class "Default")
      (node (ref "AUX2") (pin "7") (pinfunction "7_7") (pintype "passive"))
    )
    (net (code "91") (name "unconnected-(J0-*D18-Pad18)") (class "Default")
      (node (ref "J0") (pin "18") (pinfunction "*D18_18") (pintype "bidirectional"))
    )
    (net (code "92") (name "unconnected-(J0-*D19-Pad19)") (class "Default")
      (node (ref "J0") (pin "19") (pinfunction "*D19_19") (pintype "bidirectional"))
    )
    (net (code "93") (name "unconnected-(J0-*D20-Pad20)") (class "Default")
      (node (ref "J0") (pin "20") (pinfunction "*D20_20") (pintype "bidirectional"))
    )
    (net (code "94") (name "unconnected-(J0-*D21-Pad21)") (class "Default")
      (node (ref "J0") (pin "21") (pinfunction "*D21_21") (pintype "bidirectional"))
    )
    (net (code "95") (name "unconnected-(J0-D14-Pad14)") (class "Default")
      (node (ref "J0") (pin "14") (pinfunction "D14_14") (pintype "bidirectional"))
    )
    (net (code "96") (name "unconnected-(J0-D15-Pad15)") (class "Default")
      (node (ref "J0") (pin "15") (pinfunction "D15_15") (pintype "bidirectional"))
    )
    (net (code "97") (name "unconnected-(J0-D16-Pad16)") (class "Default")
      (node (ref "J0") (pin "16") (pinfunction "D16_16") (pintype "bidirectional"))
    )
    (net (code "98") (name "unconnected-(J0-D17-Pad17)") (class "Default")
      (node (ref "J0") (pin "17") (pinfunction "D17_17") (pintype "bidirectional"))
    )
    (net (code "99") (name "unconnected-(J0-PadA4)") (class "Default")
      (node (ref "J0") (pin "A4") (pinfunction "A4_A4") (pintype "bidirectional"))
    )
    (net (code "100") (name "unconnected-(J0-PadA5)") (class "Default")
      (node (ref "J0") (pin "A5") (pinfunction "A5_A5") (pintype "bidirectional"))
    )
    (net (code "101") (name "unconnected-(J0-PadA6)") (class "Default")
      (node (ref "J0") (pin "A6") (pinfunction "A6_A6") (pintype "bidirectional"))
    )
    (net (code "102") (name "unconnected-(J0-PadA7)") (class "Default")
      (node (ref "J0") (pin "A7") (pinfunction "A7_A7") (pintype "bidirectional"))
    )
    (net (code "103") (name "unconnected-(LCD-Pad7)") (class "Default")
      (node (ref "LCD") (pin "7") (pinfunction "7_7") (pintype "passive"))
    )
    (net (code "104") (name "unconnected-(LCD-Pad8)") (class "Default")
      (node (ref "LCD") (pin "8") (pinfunction "8_8") (pintype "passive"))
    )
    (net (code "105") (name "unconnected-(LCD-Pad9)") (class "Default")
      (node (ref "LCD") (pin "9") (pinfunction "9_9") (pintype "passive"))
    )
    (net (code "106") (name "unconnected-(LCD-Pad10)") (class "Default")
      (node (ref "LCD") (pin "10") (pinfunction "10_10") (pintype "passive"))
    )
    (net (code "107") (name "unconnected-(X-END-Pad1)") (class "Default")
      (node (ref "X-END") (pin "1") (pinfunction "1_1") (pintype "passive"))
    )
    (net (code "108") (name "unconnected-(X-END-Pad3)") (class "Default")
      (node (ref "X-END") (pin "3") (pinfunction "3_3") (pintype "passive"))
    )
    (net (code "109") (name "unconnected-(X-END-Pad5)") (class "Default")
      (node (ref "X-END") (pin "5") (pinfunction "5_5") (pintype "passive"))
    )
    (net (code "110") (name "unconnected-(Y-END-Pad1)") (class "Default")
      (node (ref "Y-END") (pin "1") (pinfunction "1_1") (pintype "passive"))
    )
    (net (code "111") (name "unconnected-(Y-END-Pad3)") (class "Default")
      (node (ref "Y-END") (pin "3") (pinfunction "3_3") (pintype "passive"))
    )
    (net (code "112") (name "unconnected-(Y-END-Pad5)") (class "Default")
      (node (ref "Y-END") (pin "5") (pinfunction "5_5") (pintype "passive"))
    )
    (net (code "113") (name "unconnected-(Z-END-Pad1)") (class "Default")
      (node (ref "Z-END") (pin "1") (pinfunction "1_1") (pintype "passive"))
    )
    (net (code "114") (name "unconnected-(Z-END-Pad3)") (class "Default")
      (node (ref "Z-END") (pin "3") (pinfunction "3_3") (pintype "passive"))
    )
    (net (code "115") (name "unconnected-(Z-END-Pad5)") (class "Default")
      (node (ref "Z-END") (pin "5") (pinfunction "5_5") (pintype "passive"))
    )
  )
)
